# pca20020_sheet9_interface.net
KiCad netlist of a schematic drawn in Altium Designer
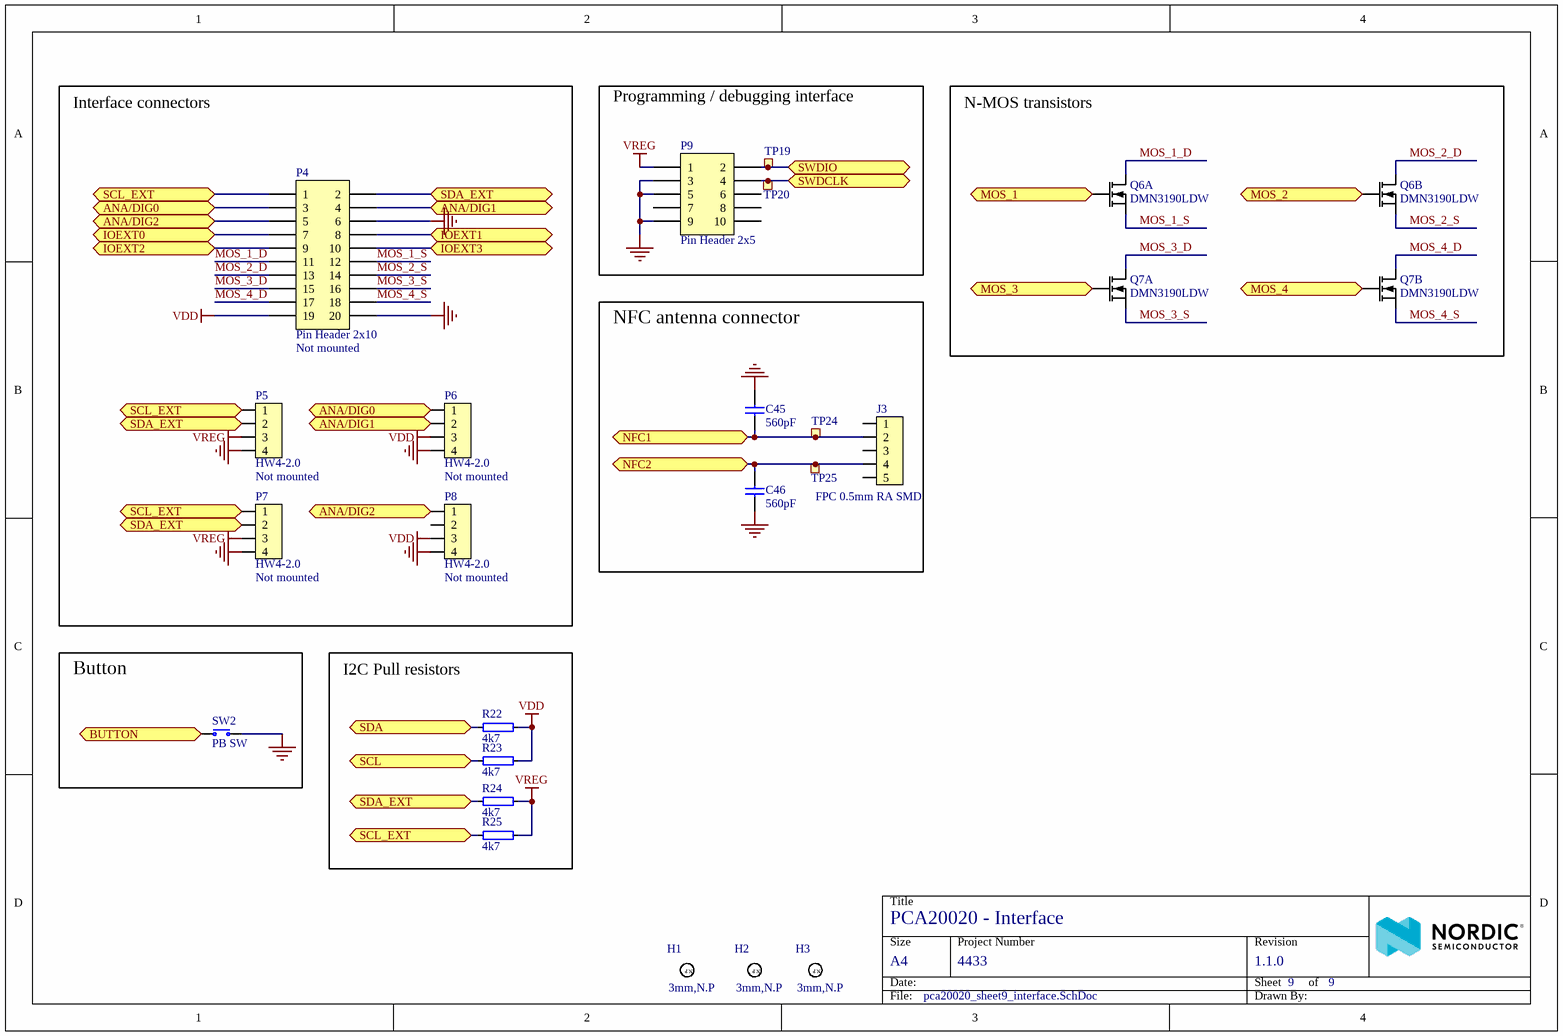
[diagram p0: pca20020_sheet9_interface.SchDoc]

(export (version "E")
  (design (tool "Eeschema 10.0.6"))
  (components
    (comp (ref "C45")
      (value "560pF")
      (footprint "CAPC1005X04L")
      (description "Capacitor, NP0, ±5%")
      (fields (field (name "PART NUMBER") "C0402-560p") (field (name "PUBLISHER") "Nordic Semiconductor"))
      (libsource (lib "Nordic Passive DB") (part "CAP"))
    )
    (comp (ref "C46")
      (value "560pF")
      (footprint "CAPC1005X04L")
      (description "Capacitor, NP0, ±5%")
      (fields (field (name "PART NUMBER") "C0402-560p") (field (name "PUBLISHER") "Nordic Semiconductor"))
      (libsource (lib "Nordic Passive DB") (part "CAP"))
    )
    (comp (ref "H1")
      (value "3mm,N.P")
      (footprint "HOLE_NP_3MM")
      (description "Regular Non-Plated, 3mm hole")
      (fields
        (field (name "PART NUMBER") "Hole_3MM_NP")
        (field (name "MANUFACTURER") "Nordic Semiconductor")
        (field (name "PUBLISHER") "Nordic Semiconductor")
      )
      (libsource (lib "Nordic Passive DB") (part "HOLE_NP"))
    )
    (comp (ref "H2")
      (value "3mm,N.P")
      (footprint "HOLE_NP_3MM")
      (description "Regular Non-Plated, 3mm hole")
      (fields
        (field (name "PART NUMBER") "Hole_3MM_NP")
        (field (name "MANUFACTURER") "Nordic Semiconductor")
        (field (name "PUBLISHER") "Nordic Semiconductor")
      )
      (libsource (lib "Nordic Passive DB") (part "HOLE_NP"))
    )
    (comp (ref "H3")
      (value "3mm,N.P")
      (footprint "HOLE_NP_3MM")
      (description "Regular Non-Plated, 3mm hole")
      (fields
        (field (name "PART NUMBER") "Hole_3MM_NP")
        (field (name "MANUFACTURER") "Nordic Semiconductor")
        (field (name "PUBLISHER") "Nordic Semiconductor")
      )
      (libsource (lib "Nordic Passive DB") (part "HOLE_NP"))
    )
    (comp (ref "J3")
      (value "FPC 0.5mm RA SMD")
      (footprint "FPC_05P-0.5mm-RA-SMD")
      (description "0.5mm FPC, 5P,Right Angle SMT,Double Contact,H=1.2mm,White, Tin plated")
      (fields
        (field (name "PART NUMBER") "FPC_05P-0.5mm-RA-SMD")
        (field (name "MANUFACTURER") "W-CON")
        (field (name "PUBLISHER") "Nordic Semiconductor")
      )
      (libsource (lib "Nordic Passive DB") (part "CONN-5"))
    )
    (comp (ref "P4")
      (value "Pin Header 2x10")
      (footprint "HDR_2x10-NC")
      (description "Pin Header 2x10, 2.54mm (100mil)")
      (fields
        (field (name "PART NUMBER") "Pin Header 2x10, N.C.")
        (field (name "ASSEMBLY") "Not mounted")
        (field (name "PUBLISHER") "Nordic Semiconductor")
      )
      (libsource (lib "Nordic Passive DB") (part "CONN-2x10"))
    )
    (comp (ref "P5")
      (value "HW4-2.0")
      (footprint "TAIFENG_HW4-2.0-NC")
      (description "4 pin, Grove DIP connector")
      (fields
        (field (name "PART NUMBER") "Taifeng_HW4-2.0, N.C.")
        (field (name "ASSEMBLY") "Not mounted")
        (field (name "MANUFACTURER") "Taifeng")
        (field (name "PUBLISHER") "Nordic Semiconductor")
      )
      (libsource (lib "Nordic Passive DB") (part "CONN-4"))
    )
    (comp (ref "P6")
      (value "HW4-2.0")
      (footprint "TAIFENG_HW4-2.0-NC")
      (description "4 pin, Grove DIP connector")
      (fields
        (field (name "PART NUMBER") "Taifeng_HW4-2.0, N.C.")
        (field (name "ASSEMBLY") "Not mounted")
        (field (name "MANUFACTURER") "Taifeng")
        (field (name "PUBLISHER") "Nordic Semiconductor")
      )
      (libsource (lib "Nordic Passive DB") (part "CONN-4"))
    )
    (comp (ref "P7")
      (value "HW4-2.0")
      (footprint "TAIFENG_HW4-2.0-NC")
      (description "4 pin, Grove DIP connector")
      (fields
        (field (name "PART NUMBER") "Taifeng_HW4-2.0, N.C.")
        (field (name "ASSEMBLY") "Not mounted")
        (field (name "MANUFACTURER") "Taifeng")
        (field (name "PUBLISHER") "Nordic Semiconductor")
      )
      (libsource (lib "Nordic Passive DB") (part "CONN-4"))
    )
    (comp (ref "P8")
      (value "HW4-2.0")
      (footprint "TAIFENG_HW4-2.0-NC")
      (description "4 pin, Grove DIP connector")
      (fields
        (field (name "PART NUMBER") "Taifeng_HW4-2.0, N.C.")
        (field (name "ASSEMBLY") "Not mounted")
        (field (name "MANUFACTURER") "Taifeng")
        (field (name "PUBLISHER") "Nordic Semiconductor")
      )
      (libsource (lib "Nordic Passive DB") (part "CONN-4"))
    )
    (comp (ref "P9")
      (value "Pin Header 2x5")
      (footprint "HDR_2x5-SMD-1.27mm-ANG")
      (description "Pin Header 2x5, 1.27mm (50mil)")
      (fields
        (field (name "PART NUMBER") "Pin Header 2x5 SMD, 1.27mm, Angled")
        (field (name "MANUFACTURER") "Samtec")
        (field (name "PUBLISHER") "Nordic Semiconductor")
      )
      (libsource (lib "Nordic Passive DB") (part "CONN-2x5"))
    )
    (comp (ref "Q6")
      (value "DMN3190LDW")
      (footprint "SOT-363")
      (description "Dual N Ch MOFET, 1A, 190mOhm, 320mW")
      (fields
        (field (name "MANUFACTURER") "Diodes Incorporated")
        (field (name "PUBLISHER") "Nordic Semiconductor")
      )
      (libsource (lib "Nordic Discrete DB") (part "T{colon}FET-N-DUAL"))
    )
    (comp (ref "Q7")
      (value "DMN3190LDW")
      (footprint "SOT-363")
      (description "Dual N Ch MOFET, 1A, 190mOhm, 320mW")
      (fields
        (field (name "MANUFACTURER") "Diodes Incorporated")
        (field (name "PUBLISHER") "Nordic Semiconductor")
      )
      (libsource (lib "Nordic Discrete DB") (part "T{colon}FET-N-DUAL"))
    )
    (comp (ref "R22")
      (value "4k7")
      (footprint "RESC1005X04L")
      (description "Resistor, ±1%, 0.063W")
      (fields (field (name "PART NUMBER") "R0402-4k7") (field (name "PUBLISHER") "Nordic Semiconductor"))
      (libsource (lib "Nordic Passive DB") (part "RES_1"))
    )
    (comp (ref "R23")
      (value "4k7")
      (footprint "RESC1005X04L")
      (description "Resistor, ±1%, 0.063W")
      (fields (field (name "PART NUMBER") "R0402-4k7") (field (name "PUBLISHER") "Nordic Semiconductor"))
      (libsource (lib "Nordic Passive DB") (part "RES_1"))
    )
    (comp (ref "R24")
      (value "4k7")
      (footprint "RESC1005X04L")
      (description "Resistor, ±1%, 0.063W")
      (fields (field (name "PART NUMBER") "R0402-4k7") (field (name "PUBLISHER") "Nordic Semiconductor"))
      (libsource (lib "Nordic Passive DB") (part "RES_1"))
    )
    (comp (ref "R25")
      (value "4k7")
      (footprint "RESC1005X04L")
      (description "Resistor, ±1%, 0.063W")
      (fields (field (name "PART NUMBER") "R0402-4k7") (field (name "PUBLISHER") "Nordic Semiconductor"))
      (libsource (lib "Nordic Passive DB") (part "RES_1"))
    )
    (comp (ref "SW2")
      (value "PB SW")
      (footprint "Switch-PB-6.2x6.3mm-SMD")
      (description "Tactile Switch, SPNO, SMD, 160gf, 6.2x6.3x2.5mm")
      (fields
        (field (name "PART NUMBER") "Switch-PB-6.2x6.3mm-SMD")
        (field (name "MANUFACTURER") "Dailywell")
        (field (name "PUBLISHER") "Nordic Semiconductor")
      )
      (libsource (lib "Nordic Discrete DB") (part "SW-PB"))
    )
    (comp (ref "TP19")
      (value "Ø1.5mm,SMD")
      (footprint "TP_SMD_Ø1.5mm")
      (description "1.0mm circular SMD testpad")
      (fields
        (field (name "PART NUMBER") "TP_SMD_Ø1.5MM")
        (field (name "MANUFACTURER") "Nordic Semiconductor")
        (field (name "PUBLISHER") "Nordic Semiconductor")
      )
      (libsource (lib "") (part "TESTPAD_1"))
    )
    (comp (ref "TP20")
      (value "Ø1.5mm,SMD")
      (footprint "TP_SMD_Ø1.5mm")
      (description "1.0mm circular SMD testpad")
      (fields
        (field (name "PART NUMBER") "TP_SMD_Ø1.5MM")
        (field (name "MANUFACTURER") "Nordic Semiconductor")
        (field (name "PUBLISHER") "Nordic Semiconductor")
      )
      (libsource (lib "Nordic Passive DB") (part "TESTPAD"))
    )
    (comp (ref "TP24")
      (value "Ø1.0mm,SMD")
      (footprint "TP_SMD_Ø1.0mm")
      (description "1.0mm circular SMD testpad")
      (fields
        (field (name "PART NUMBER") "TP_SMD_Ø1.0MM")
        (field (name "MANUFACTURER") "Nordic Semiconductor")
        (field (name "PUBLISHER") "Nordic Semiconductor")
      )
      (libsource (lib "") (part "TESTPAD_1"))
    )
    (comp (ref "TP25")
      (value "Ø1.0mm,SMD")
      (footprint "TP_SMD_Ø1.0mm")
      (description "1.0mm circular SMD testpad")
      (fields
        (field (name "PART NUMBER") "TP_SMD_Ø1.0MM")
        (field (name "MANUFACTURER") "Nordic Semiconductor")
        (field (name "PUBLISHER") "Nordic Semiconductor")
      )
      (libsource (lib "Nordic Passive DB") (part "TESTPAD"))
    )
  )
  (nets
    (net (code "1") (name "/ANA{slash}DIG0") (class "Default")
      (node (ref "P4") (pin "3") (pinfunction "3_3") (pintype "passive"))
      (node (ref "P6") (pin "1") (pinfunction "1_1") (pintype "passive"))
    )
    (net (code "2") (name "/ANA{slash}DIG1") (class "Default")
      (node (ref "P4") (pin "4") (pinfunction "4_4") (pintype "passive"))
      (node (ref "P6") (pin "2") (pinfunction "2_2") (pintype "passive"))
    )
    (net (code "3") (name "/ANA{slash}DIG2") (class "Default")
      (node (ref "P4") (pin "5") (pinfunction "5_5") (pintype "passive"))
      (node (ref "P8") (pin "1") (pinfunction "1_1") (pintype "passive"))
    )
    (net (code "4") (name "/BUTTON") (class "Default")
      (node (ref "SW2") (pin "2") (pinfunction "COM_2") (pintype "passive"))
    )
    (net (code "5") (name "/IOEXT0") (class "Default")
      (node (ref "P4") (pin "7") (pinfunction "7_7") (pintype "passive"))
    )
    (net (code "6") (name "/IOEXT1") (class "Default")
      (node (ref "P4") (pin "8") (pinfunction "8_8") (pintype "passive"))
    )
    (net (code "7") (name "/IOEXT2") (class "Default")
      (node (ref "P4") (pin "9") (pinfunction "9_9") (pintype "passive"))
    )
    (net (code "8") (name "/IOEXT3") (class "Default")
      (node (ref "P4") (pin "10") (pinfunction "10_10") (pintype "passive"))
    )
    (net (code "9") (name "/MOS_1") (class "Default")
      (node (ref "Q6") (pin "2") (pinfunction "G1_2") (pintype "passive"))
    )
    (net (code "10") (name "/MOS_1_D") (class "Default")
      (node (ref "P4") (pin "11") (pinfunction "11_11") (pintype "passive"))
      (node (ref "Q6") (pin "6") (pinfunction "D1_6") (pintype "passive"))
    )
    (net (code "11") (name "/MOS_1_S") (class "Default")
      (node (ref "P4") (pin "12") (pinfunction "12_12") (pintype "passive"))
      (node (ref "Q6") (pin "1") (pinfunction "S1_1") (pintype "passive"))
    )
    (net (code "12") (name "/MOS_2") (class "Default")
      (node (ref "Q6") (pin "5") (pinfunction "G2_5") (pintype "passive"))
    )
    (net (code "13") (name "/MOS_2_D") (class "Default")
      (node (ref "P4") (pin "13") (pinfunction "13_13") (pintype "passive"))
      (node (ref "Q6") (pin "3") (pinfunction "D2_3") (pintype "passive"))
    )
    (net (code "14") (name "/MOS_2_S") (class "Default")
      (node (ref "P4") (pin "14") (pinfunction "14_14") (pintype "passive"))
      (node (ref "Q6") (pin "4") (pinfunction "S2_4") (pintype "passive"))
    )
    (net (code "15") (name "/MOS_3") (class "Default")
      (node (ref "Q7") (pin "2") (pinfunction "G1_2") (pintype "passive"))
    )
    (net (code "16") (name "/MOS_3_D") (class "Default")
      (node (ref "P4") (pin "15") (pinfunction "15_15") (pintype "passive"))
      (node (ref "Q7") (pin "6") (pinfunction "D1_6") (pintype "passive"))
    )
    (net (code "17") (name "/MOS_3_S") (class "Default")
      (node (ref "P4") (pin "16") (pinfunction "16_16") (pintype "passive"))
      (node (ref "Q7") (pin "1") (pinfunction "S1_1") (pintype "passive"))
    )
    (net (code "18") (name "/MOS_4") (class "Default")
      (node (ref "Q7") (pin "5") (pinfunction "G2_5") (pintype "passive"))
    )
    (net (code "19") (name "/MOS_4_D") (class "Default")
      (node (ref "P4") (pin "17") (pinfunction "17_17") (pintype "passive"))
      (node (ref "Q7") (pin "3") (pinfunction "D2_3") (pintype "passive"))
    )
    (net (code "20") (name "/MOS_4_S") (class "Default")
      (node (ref "P4") (pin "18") (pinfunction "18_18") (pintype "passive"))
      (node (ref "Q7") (pin "4") (pinfunction "S2_4") (pintype "passive"))
    )
    (net (code "21") (name "/NFC1") (class "Default")
      (node (ref "C45") (pin "1") (pinfunction "1_1") (pintype "passive"))
      (node (ref "J3") (pin "2") (pinfunction "2_2") (pintype "passive"))
      (node (ref "TP24") (pin "1") (pinfunction "1_1") (pintype "passive"))
    )
    (net (code "22") (name "/NFC2") (class "Default")
      (node (ref "C46") (pin "2") (pinfunction "2_2") (pintype "passive"))
      (node (ref "J3") (pin "4") (pinfunction "4_4") (pintype "passive"))
      (node (ref "TP25") (pin "1") (pinfunction "1_1") (pintype "passive"))
    )
    (net (code "23") (name "/SCL") (class "Default")
      (node (ref "R23") (pin "2") (pinfunction "2_2") (pintype "passive"))
    )
    (net (code "24") (name "/SCL_EXT") (class "Default")
      (node (ref "P4") (pin "1") (pinfunction "1_1") (pintype "passive"))
      (node (ref "P5") (pin "1") (pinfunction "1_1") (pintype "passive"))
      (node (ref "P7") (pin "1") (pinfunction "1_1") (pintype "passive"))
      (node (ref "R25") (pin "2") (pinfunction "2_2") (pintype "passive"))
    )
    (net (code "25") (name "/SDA") (class "Default")
      (node (ref "R22") (pin "2") (pinfunction "2_2") (pintype "passive"))
    )
    (net (code "26") (name "/SDA_EXT") (class "Default")
      (node (ref "P4") (pin "2") (pinfunction "2_2") (pintype "passive"))
      (node (ref "P5") (pin "2") (pinfunction "2_2") (pintype "passive"))
      (node (ref "P7") (pin "2") (pinfunction "2_2") (pintype "passive"))
      (node (ref "R24") (pin "2") (pinfunction "2_2") (pintype "passive"))
    )
    (net (code "27") (name "/SWDCLK") (class "Default")
      (node (ref "P9") (pin "4") (pinfunction "4_4") (pintype "passive"))
      (node (ref "TP20") (pin "1") (pinfunction "1_1") (pintype "passive"))
    )
    (net (code "28") (name "/SWDIO") (class "Default")
      (node (ref "P9") (pin "2") (pinfunction "2_2") (pintype "passive"))
      (node (ref "TP19") (pin "1") (pinfunction "1_1") (pintype "passive"))
    )
    (net (code "29") (name "GND") (class "Default")
      (node (ref "C45") (pin "2") (pinfunction "2_2") (pintype "passive"))
      (node (ref "C46") (pin "1") (pinfunction "1_1") (pintype "passive"))
      (node (ref "P4") (pin "20") (pinfunction "20_20") (pintype "passive"))
      (node (ref "P4") (pin "6") (pinfunction "6_6") (pintype "passive"))
      (node (ref "P5") (pin "4") (pinfunction "4_4") (pintype "passive"))
      (node (ref "P6") (pin "4") (pinfunction "4_4") (pintype "passive"))
      (node (ref "P7") (pin "4") (pinfunction "4_4") (pintype "passive"))
      (node (ref "P8") (pin "4") (pinfunction "4_4") (pintype "passive"))
      (node (ref "P9") (pin "3") (pinfunction "3_3") (pintype "passive"))
      (node (ref "P9") (pin "5") (pinfunction "5_5") (pintype "passive"))
      (node (ref "P9") (pin "9") (pinfunction "9_9") (pintype "passive"))
      (node (ref "SW2") (pin "1") (pinfunction "N.O_1") (pintype "passive"))
    )
    (net (code "30") (name "VDD") (class "Default")
      (node (ref "P4") (pin "19") (pinfunction "19_19") (pintype "passive"))
      (node (ref "P6") (pin "3") (pinfunction "3_3") (pintype "passive"))
      (node (ref "P8") (pin "3") (pinfunction "3_3") (pintype "passive"))
      (node (ref "R22") (pin "1") (pinfunction "1_1") (pintype "passive"))
      (node (ref "R23") (pin "1") (pinfunction "1_1") (pintype "passive"))
    )
    (net (code "31") (name "VREG") (class "Default")
      (node (ref "P5") (pin "3") (pinfunction "3_3") (pintype "passive"))
      (node (ref "P7") (pin "3") (pinfunction "3_3") (pintype "passive"))
      (node (ref "P9") (pin "1") (pinfunction "1_1") (pintype "passive"))
      (node (ref "R24") (pin "1") (pinfunction "1_1") (pintype "passive"))
      (node (ref "R25") (pin "1") (pinfunction "1_1") (pintype "passive"))
    )
    (net (code "32") (name "unconnected-(H1-Pad1)") (class "Default")
      (node (ref "H1") (pin "1") (pinfunction "1_1") (pintype "passive"))
    )
    (net (code "33") (name "unconnected-(H2-Pad1)") (class "Default")
      (node (ref "H2") (pin "1") (pinfunction "1_1") (pintype "passive"))
    )
    (net (code "34") (name "unconnected-(H3-Pad1)") (class "Default")
      (node (ref "H3") (pin "1") (pinfunction "1_1") (pintype "passive"))
    )
    (net (code "35") (name "unconnected-(J3-Pad1)") (class "Default")
      (node (ref "J3") (pin "1") (pinfunction "1_1") (pintype "passive"))
    )
    (net (code "36") (name "unconnected-(J3-Pad3)") (class "Default")
      (node (ref "J3") (pin "3") (pinfunction "3_3") (pintype "passive"))
    )
    (net (code "37") (name "unconnected-(J3-Pad5)") (class "Default")
      (node (ref "J3") (pin "5") (pinfunction "5_5") (pintype "passive"))
    )
    (net (code "38") (name "unconnected-(P8-Pad2)") (class "Default")
      (node (ref "P8") (pin "2") (pinfunction "2_2") (pintype "passive"))
    )
    (net (code "39") (name "unconnected-(P9-Pad6)") (class "Default")
      (node (ref "P9") (pin "6") (pinfunction "6_6") (pintype "passive"))
    )
    (net (code "40") (name "unconnected-(P9-Pad7)") (class "Default")
      (node (ref "P9") (pin "7") (pinfunction "7_7") (pintype "passive"))
    )
    (net (code "41") (name "unconnected-(P9-Pad8)") (class "Default")
      (node (ref "P9") (pin "8") (pinfunction "8_8") (pintype "passive"))
    )
    (net (code "42") (name "unconnected-(P9-Pad10)") (class "Default")
      (node (ref "P9") (pin "10") (pinfunction "10_10") (pintype "passive"))
    )
  )
)
